# RJ45.net
KiCad netlist of a schematic drawn in Altium Designer
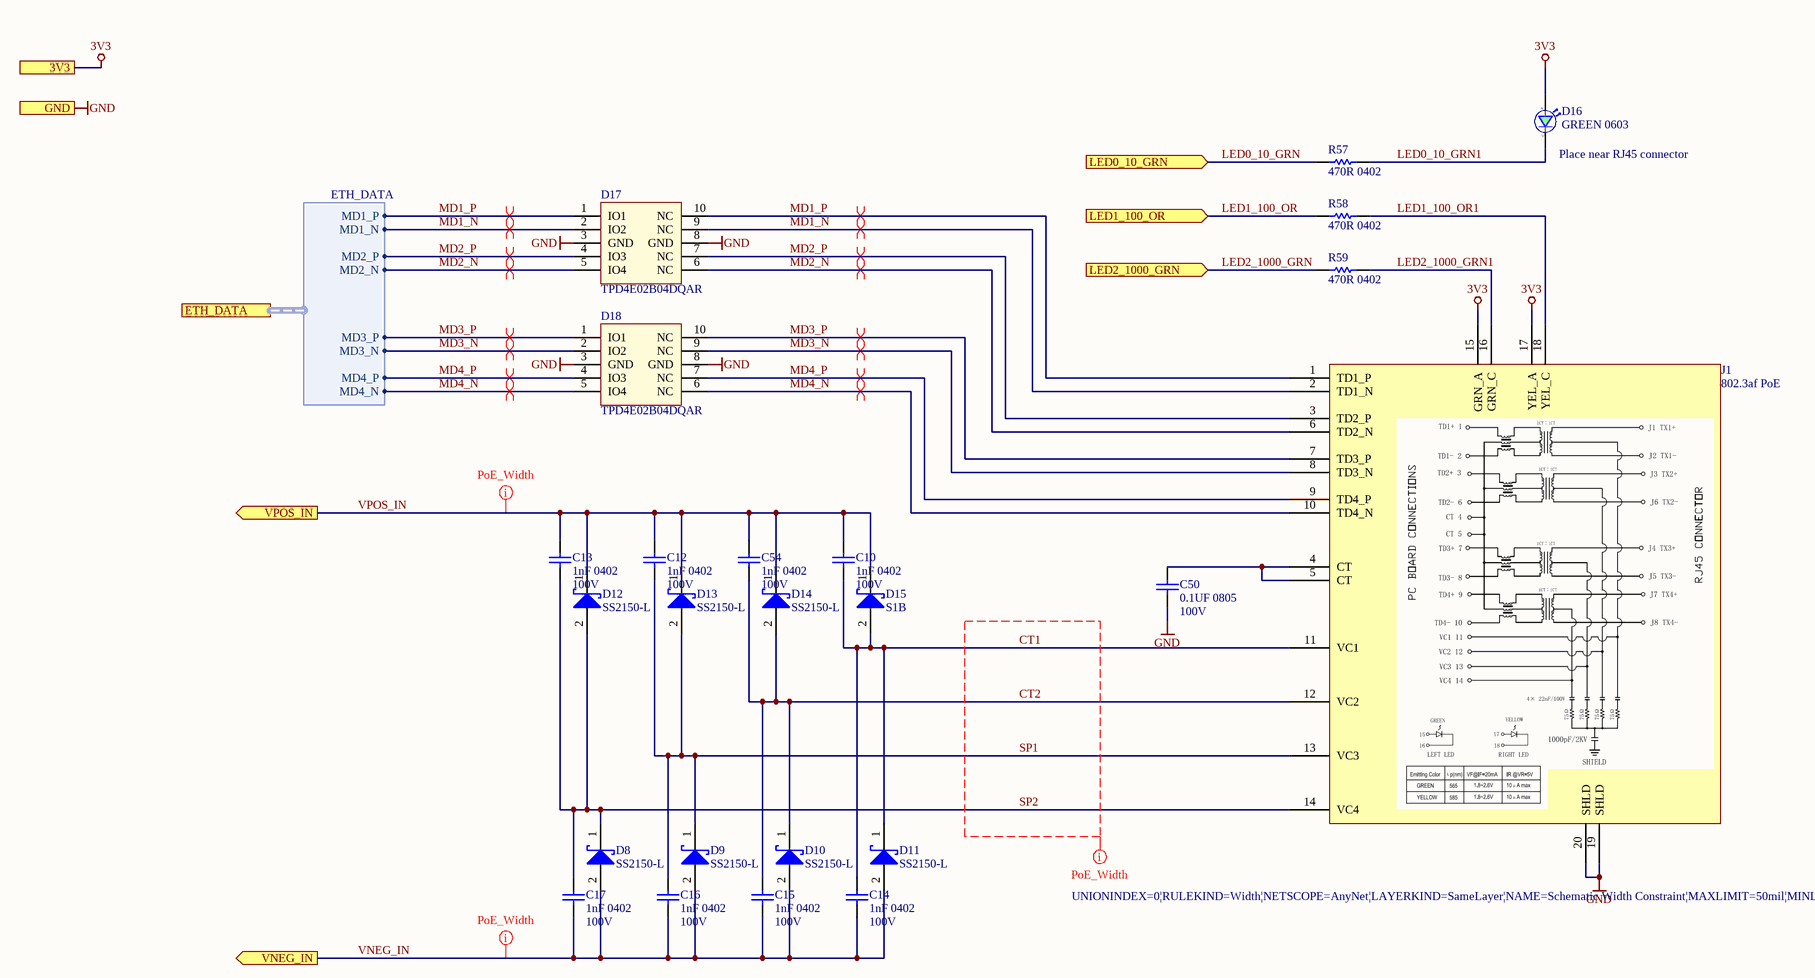
[diagram p0: RJ45.SchDoc]

(export (version "E")
  (design (tool "Eeschema 10.0.6"))
  (components
    (comp (ref "C10")
      (value "1nF 0402")
      (footprint "CAP_Altium_Vault_Generic:CAPC0402(1005)60_N")
      (description "CAP CER 1000PF 100V X7R 0402")
      (fields (field (name "TOLERANCE") "10%") (field (name "VOLTAGE") "100V"))
      (libsource (lib "PCBProject") (part "GRM155R72A102KA01D"))
    )
    (comp (ref "C12")
      (value "1nF 0402")
      (footprint "CAP_Altium_Vault_Generic:CAPC0402(1005)60_N")
      (description "CAP CER 1000PF 100V X7R 0402")
      (fields (field (name "TOLERANCE") "10%") (field (name "VOLTAGE") "100V"))
      (libsource (lib "PCBProject") (part "GRM155R72A102KA01D"))
    )
    (comp (ref "C13")
      (value "1nF 0402")
      (footprint "CAP_Altium_Vault_Generic:CAPC0402(1005)60_N")
      (description "CAP CER 1000PF 100V X7R 0402")
      (fields (field (name "TOLERANCE") "10%") (field (name "VOLTAGE") "100V"))
      (libsource (lib "PCBProject") (part "GRM155R72A102KA01D"))
    )
    (comp (ref "C14")
      (value "1nF 0402")
      (footprint "CAP_Altium_Vault_Generic:CAPC0402(1005)60_N")
      (description "CAP CER 1000PF 100V X7R 0402")
      (fields (field (name "TOLERANCE") "10%") (field (name "VOLTAGE") "100V"))
      (libsource (lib "PCBProject") (part "GRM155R72A102KA01D"))
    )
    (comp (ref "C15")
      (value "1nF 0402")
      (footprint "CAP_Altium_Vault_Generic:CAPC0402(1005)60_N")
      (description "CAP CER 1000PF 100V X7R 0402")
      (fields (field (name "TOLERANCE") "10%") (field (name "VOLTAGE") "100V"))
      (libsource (lib "PCBProject") (part "GRM155R72A102KA01D"))
    )
    (comp (ref "C16")
      (value "1nF 0402")
      (footprint "CAP_Altium_Vault_Generic:CAPC0402(1005)60_N")
      (description "CAP CER 1000PF 100V X7R 0402")
      (fields (field (name "TOLERANCE") "10%") (field (name "VOLTAGE") "100V"))
      (libsource (lib "PCBProject") (part "GRM155R72A102KA01D"))
    )
    (comp (ref "C17")
      (value "1nF 0402")
      (footprint "CAP_Altium_Vault_Generic:CAPC0402(1005)60_N")
      (description "CAP CER 1000PF 100V X7R 0402")
      (fields (field (name "TOLERANCE") "10%") (field (name "VOLTAGE") "100V"))
      (libsource (lib "PCBProject") (part "GRM155R72A102KA01D"))
    )
    (comp (ref "C50")
      (value "0.1UF 0805")
      (footprint "CAP_Altium_Vault_Generic:CAPC0805(2012)145_N")
      (description "CAP CER 0.1UF 100V X7R 0805")
      (fields (field (name "TOLERANCE") "10%") (field (name "VOLTAGE RATING") "100V"))
      (libsource (lib "PCBProject") (part "CL21B104KCFNNNE"))
    )
    (comp (ref "C54")
      (value "1nF 0402")
      (footprint "CAP_Altium_Vault_Generic:CAPC0402(1005)60_N")
      (description "CAP CER 1000PF 100V X7R 0402")
      (fields (field (name "TOLERANCE") "10%") (field (name "VOLTAGE") "100V"))
      (libsource (lib "PCBProject") (part "GRM155R72A102KA01D"))
    )
    (comp (ref "D8")
      (value "SS2150-L")
      (footprint "BW2098POE:SB1")
      (description "DIODE GEN PURP 100V 1A SMA")
      (libsource (lib "BW2098POE") (part "S1B"))
    )
    (comp (ref "D9")
      (value "SS2150-L")
      (footprint "BW2098POE:SB1")
      (description "DIODE GEN PURP 100V 1A SMA")
      (libsource (lib "BW2098POE") (part "S1B"))
    )
    (comp (ref "D10")
      (value "SS2150-L")
      (footprint "BW2098POE:SB1")
      (description "DIODE GEN PURP 100V 1A SMA")
      (libsource (lib "BW2098POE") (part "S1B"))
    )
    (comp (ref "D11")
      (value "SS2150-L")
      (footprint "BW2098POE:SB1")
      (description "DIODE GEN PURP 100V 1A SMA")
      (libsource (lib "BW2098POE") (part "S1B"))
    )
    (comp (ref "D12")
      (value "SS2150-L")
      (footprint "BW2098POE:SB1")
      (description "DIODE GEN PURP 100V 1A SMA")
      (libsource (lib "BW2098POE") (part "S1B"))
    )
    (comp (ref "D13")
      (value "SS2150-L")
      (footprint "BW2098POE:SB1")
      (description "DIODE GEN PURP 100V 1A SMA")
      (libsource (lib "BW2098POE") (part "S1B"))
    )
    (comp (ref "D14")
      (value "SS2150-L")
      (footprint "BW2098POE:SB1")
      (description "DIODE GEN PURP 100V 1A SMA")
      (libsource (lib "BW2098POE") (part "S1B"))
    )
    (comp (ref "D15")
      (value "S1B")
      (footprint "BW2098POE:SB1")
      (description "DIODE GEN PURP 100V 1A SMA")
      (libsource (lib "BW2098POE") (part "S1B"))
    )
    (comp (ref "D16")
      (value "GREEN 0603")
      (footprint "LuxonisMaster:SML_D1xx8W")
      (description "LED GREEN DIFFUSED 0603 SMD Green 572nm LED Indication - Discrete 2.2V 0603 (1608 Metric)")
      (fields (field (name "MANUFACTURER") "Rohm") (field (name "MANUFACTURER PART NUMBER") "SML-D12M8WT86"))
      (libsource (lib "LuxonisMaster") (part "SML-D12M8WT86"))
    )
    (comp (ref "D17")
      (value "TPD4E02B04DQAR")
      (footprint "LuxonisMaster:TPD4E02B04DQAR")
      (libsource (lib "LuxonisMaster") (part "TPD4E02B04DQAR"))
    )
    (comp (ref "D18")
      (value "TPD4E02B04DQAR")
      (footprint "LuxonisMaster:TPD4E02B04DQAR")
      (libsource (lib "LuxonisMaster") (part "TPD4E02B04DQAR"))
    )
    (comp (ref "J1")
      (value "802.3af PoE")
      (footprint "BW2098POE:TRJG0926HENL")
      (description "CONN MAGJACK 1PORT 1000 BASET")
      (libsource (lib "BW2098POE") (part "TRJG0926HENL"))
    )
    (comp (ref "R57")
      (value "470R 0402")
      (footprint "RES_Altium_Vault_Generic:RESC0402(1005)_N")
      (description "RES SMD 470 OHM 1% 1/16W 0402")
      (fields (field (name "TOLERANCE") "1%"))
      (libsource (lib "LuxonisMaster") (part "CRCW0402470RFKED"))
    )
    (comp (ref "R58")
      (value "470R 0402")
      (footprint "RES_Altium_Vault_Generic:RESC0402(1005)_N")
      (description "RES SMD 470 OHM 1% 1/16W 0402")
      (fields (field (name "TOLERANCE") "1%"))
      (libsource (lib "LuxonisMaster") (part "CRCW0402470RFKED"))
    )
    (comp (ref "R59")
      (value "470R 0402")
      (footprint "RES_Altium_Vault_Generic:RESC0402(1005)_N")
      (description "RES SMD 470 OHM 1% 1/16W 0402")
      (fields (field (name "TOLERANCE") "1%"))
      (libsource (lib "LuxonisMaster") (part "CRCW0402470RFKED"))
    )
  )
  (nets
    (net (code "2") (name "/CT1") (class "Default")
      (node (ref "C10") (pin "1") (pinfunction "1_1") (pintype "passive"))
      (node (ref "C14") (pin "2") (pinfunction "2_2") (pintype "passive"))
      (node (ref "D11") (pin "1") (pinfunction "K_1") (pintype "passive"))
      (node (ref "D15") (pin "2") (pinfunction "A_2") (pintype "passive"))
      (node (ref "J1") (pin "11") (pinfunction "VC1_11") (pintype "passive"))
    )
    (net (code "3") (name "/CT2") (class "Default")
      (node (ref "C15") (pin "2") (pinfunction "2_2") (pintype "passive"))
      (node (ref "C54") (pin "1") (pinfunction "1_1") (pintype "passive"))
      (node (ref "D10") (pin "1") (pinfunction "K_1") (pintype "passive"))
      (node (ref "D14") (pin "2") (pinfunction "A_2") (pintype "passive"))
      (node (ref "J1") (pin "12") (pinfunction "VC2_12") (pintype "passive"))
    )
    (net (code "4") (name "/LED0_10_GRN") (class "Default")
      (node (ref "R57") (pin "1") (pinfunction "1_1") (pintype "passive"))
    )
    (net (code "5") (name "/LED0_10_GRN1") (class "Default")
      (node (ref "D16") (pin "1") (pinfunction "C_1") (pintype "passive"))
      (node (ref "R57") (pin "2") (pinfunction "2_2") (pintype "passive"))
    )
    (net (code "6") (name "/LED1_100_OR") (class "Default")
      (node (ref "R58") (pin "1") (pinfunction "1_1") (pintype "passive"))
    )
    (net (code "7") (name "/LED1_100_OR1") (class "Default")
      (node (ref "J1") (pin "18") (pinfunction "YEL_C_18") (pintype "passive"))
      (node (ref "R58") (pin "2") (pinfunction "2_2") (pintype "passive"))
    )
    (net (code "8") (name "/LED2_1000_GRN") (class "Default")
      (node (ref "R59") (pin "1") (pinfunction "1_1") (pintype "passive"))
    )
    (net (code "9") (name "/LED2_1000_GRN1") (class "Default")
      (node (ref "J1") (pin "16") (pinfunction "GRN_C_16") (pintype "passive"))
      (node (ref "R59") (pin "2") (pinfunction "2_2") (pintype "passive"))
    )
    (net (code "10") (name "/MD1_N") (class "Default")
      (node (ref "D17") (pin "2") (pinfunction "IO2_2") (pintype "passive"))
      (node (ref "D17") (pin "9") (pinfunction "NC_9") (pintype "passive"))
      (node (ref "J1") (pin "2") (pinfunction "TD1_N_2") (pintype "passive"))
    )
    (net (code "11") (name "/MD1_P") (class "Default")
      (node (ref "D17") (pin "1") (pinfunction "IO1_1") (pintype "passive"))
      (node (ref "D17") (pin "10") (pinfunction "NC_10") (pintype "passive"))
      (node (ref "J1") (pin "1") (pinfunction "TD1_P_1") (pintype "passive"))
    )
    (net (code "12") (name "/MD2_N") (class "Default")
      (node (ref "D17") (pin "5") (pinfunction "IO4_5") (pintype "passive"))
      (node (ref "D17") (pin "6") (pinfunction "NC_6") (pintype "passive"))
      (node (ref "J1") (pin "6") (pinfunction "TD2_N_6") (pintype "passive"))
    )
    (net (code "13") (name "/MD2_P") (class "Default")
      (node (ref "D17") (pin "4") (pinfunction "IO3_4") (pintype "passive"))
      (node (ref "D17") (pin "7") (pinfunction "NC_7") (pintype "passive"))
      (node (ref "J1") (pin "3") (pinfunction "TD2_P_3") (pintype "passive"))
    )
    (net (code "14") (name "/MD3_N") (class "Default")
      (node (ref "D18") (pin "2") (pinfunction "IO2_2") (pintype "passive"))
      (node (ref "D18") (pin "9") (pinfunction "NC_9") (pintype "passive"))
      (node (ref "J1") (pin "8") (pinfunction "TD3_N_8") (pintype "passive"))
    )
    (net (code "15") (name "/MD3_P") (class "Default")
      (node (ref "D18") (pin "1") (pinfunction "IO1_1") (pintype "passive"))
      (node (ref "D18") (pin "10") (pinfunction "NC_10") (pintype "passive"))
      (node (ref "J1") (pin "7") (pinfunction "TD3_P_7") (pintype "passive"))
    )
    (net (code "16") (name "/MD4_N") (class "Default")
      (node (ref "D18") (pin "5") (pinfunction "IO4_5") (pintype "passive"))
      (node (ref "D18") (pin "6") (pinfunction "NC_6") (pintype "passive"))
      (node (ref "J1") (pin "10") (pinfunction "TD4_N_10") (pintype "passive"))
    )
    (net (code "17") (name "/MD4_P") (class "Default")
      (node (ref "D18") (pin "4") (pinfunction "IO3_4") (pintype "passive"))
      (node (ref "D18") (pin "7") (pinfunction "NC_7") (pintype "passive"))
      (node (ref "J1") (pin "9") (pinfunction "TD4_P_9") (pintype "passive"))
    )
    (net (code "18") (name "/SP1") (class "Default")
      (node (ref "C12") (pin "1") (pinfunction "1_1") (pintype "passive"))
      (node (ref "C16") (pin "2") (pinfunction "2_2") (pintype "passive"))
      (node (ref "D13") (pin "2") (pinfunction "A_2") (pintype "passive"))
      (node (ref "D9") (pin "1") (pinfunction "K_1") (pintype "passive"))
      (node (ref "J1") (pin "13") (pinfunction "VC3_13") (pintype "passive"))
    )
    (net (code "19") (name "/SP2") (class "Default")
      (node (ref "C13") (pin "1") (pinfunction "1_1") (pintype "passive"))
      (node (ref "C17") (pin "2") (pinfunction "2_2") (pintype "passive"))
      (node (ref "D12") (pin "2") (pinfunction "A_2") (pintype "passive"))
      (node (ref "D8") (pin "1") (pinfunction "K_1") (pintype "passive"))
      (node (ref "J1") (pin "14") (pinfunction "VC4_14") (pintype "passive"))
    )
    (net (code "20") (name "/VNEG_IN") (class "Default")
      (node (ref "C14") (pin "1") (pinfunction "1_1") (pintype "passive"))
      (node (ref "C15") (pin "1") (pinfunction "1_1") (pintype "passive"))
      (node (ref "C16") (pin "1") (pinfunction "1_1") (pintype "passive"))
      (node (ref "C17") (pin "1") (pinfunction "1_1") (pintype "passive"))
      (node (ref "D10") (pin "2") (pinfunction "A_2") (pintype "passive"))
      (node (ref "D11") (pin "2") (pinfunction "A_2") (pintype "passive"))
      (node (ref "D8") (pin "2") (pinfunction "A_2") (pintype "passive"))
      (node (ref "D9") (pin "2") (pinfunction "A_2") (pintype "passive"))
    )
    (net (code "21") (name "/VPOS_IN") (class "Default")
      (node (ref "C10") (pin "2") (pinfunction "2_2") (pintype "passive"))
      (node (ref "C12") (pin "2") (pinfunction "2_2") (pintype "passive"))
      (node (ref "C13") (pin "2") (pinfunction "2_2") (pintype "passive"))
      (node (ref "C54") (pin "2") (pinfunction "2_2") (pintype "passive"))
      (node (ref "D12") (pin "1") (pinfunction "K_1") (pintype "passive"))
      (node (ref "D13") (pin "1") (pinfunction "K_1") (pintype "passive"))
      (node (ref "D14") (pin "1") (pinfunction "K_1") (pintype "passive"))
      (node (ref "D15") (pin "1") (pinfunction "K_1") (pintype "passive"))
    )
    (net (code "23") (name "3V3") (class "Default")
      (node (ref "D16") (pin "2") (pinfunction "A_2") (pintype "passive"))
      (node (ref "J1") (pin "15") (pinfunction "GRN_A_15") (pintype "passive"))
      (node (ref "J1") (pin "17") (pinfunction "YEL_A_17") (pintype "passive"))
    )
    (net (code "24") (name "GND") (class "Default")
      (node (ref "C50") (pin "1") (pinfunction "1_1") (pintype "passive"))
      (node (ref "D17") (pin "3") (pinfunction "GND_3") (pintype "passive"))
      (node (ref "D17") (pin "8") (pinfunction "GND_8") (pintype "passive"))
      (node (ref "D18") (pin "3") (pinfunction "GND_3") (pintype "passive"))
      (node (ref "D18") (pin "8") (pinfunction "GND_8") (pintype "passive"))
      (node (ref "J1") (pin "19") (pinfunction "SHLD_19") (pintype "passive"))
      (node (ref "J1") (pin "20") (pinfunction "SHLD_20") (pintype "passive"))
    )
    (net (code "25") (name "Net-(C50-Pad2)") (class "Default")
      (node (ref "C50") (pin "2") (pinfunction "2_2") (pintype "passive"))
      (node (ref "J1") (pin "4") (pinfunction "CT_4") (pintype "passive"))
      (node (ref "J1") (pin "5") (pinfunction "CT_5") (pintype "passive"))
    )
  )
)
